# ultra_wideband.net
KiCad netlist of a schematic drawn in Altium Designer
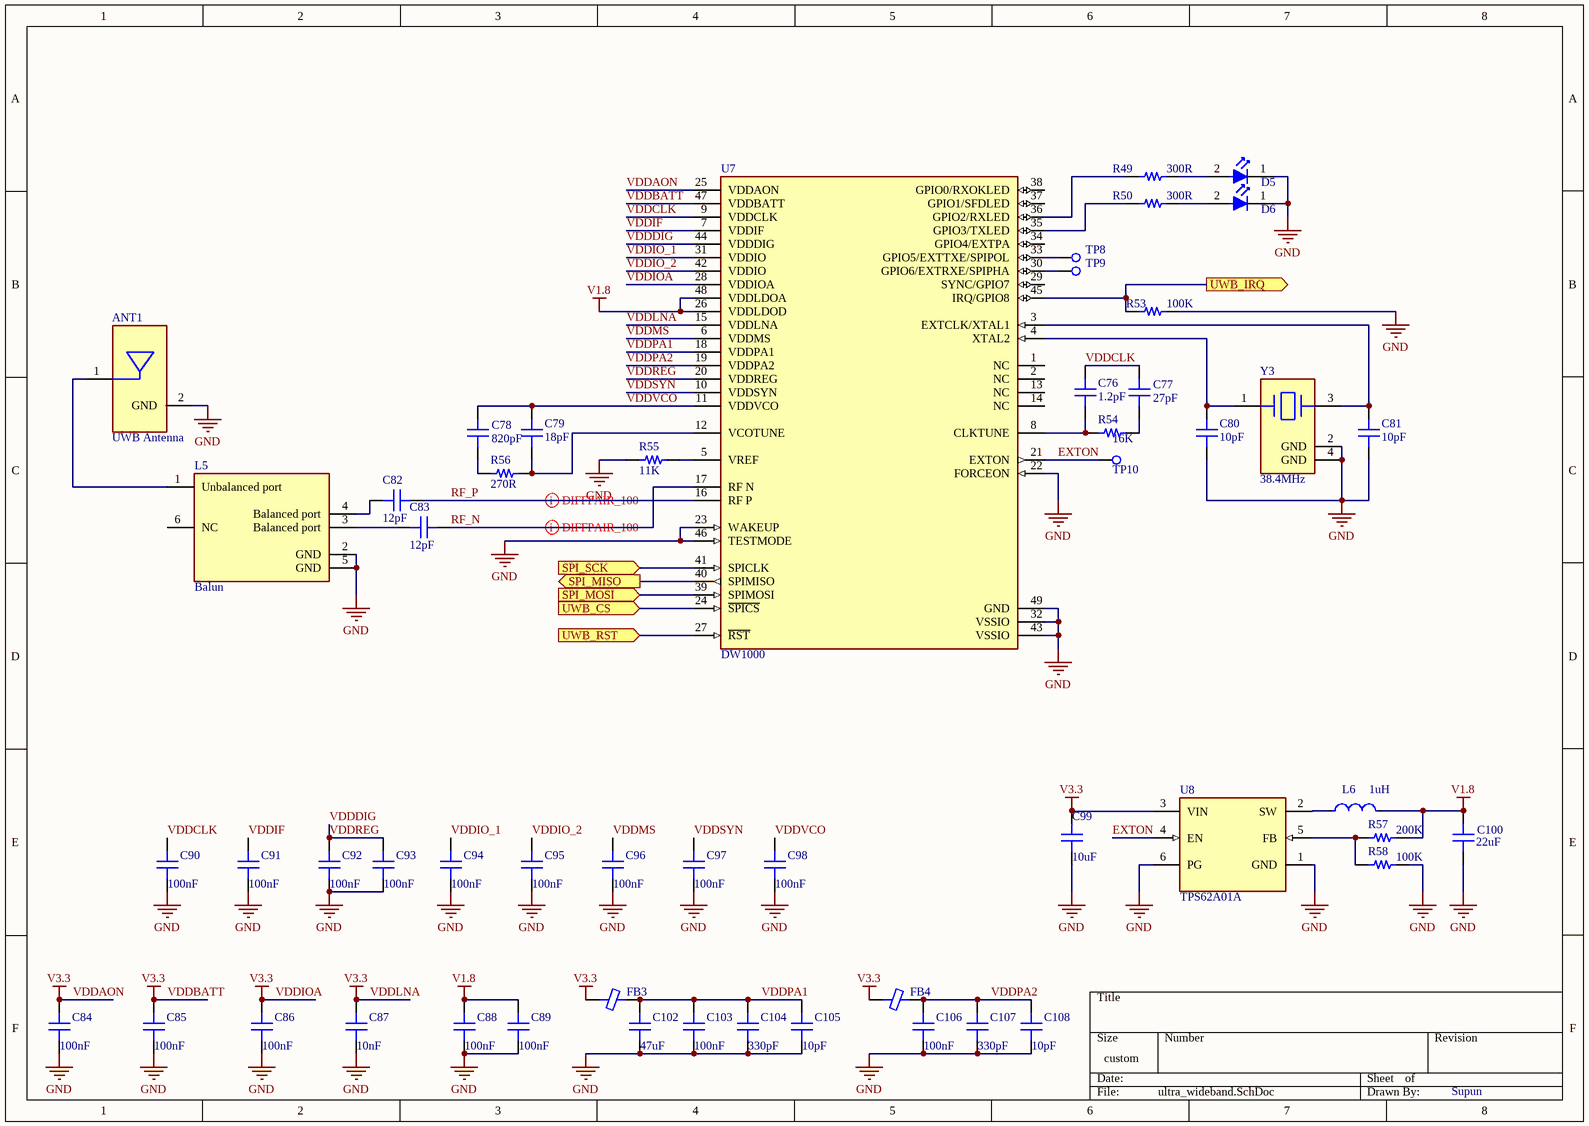
[diagram p0: ultra_wideband.SchDoc]

(export (version "E")
  (design (tool "Eeschema 10.0.6"))
  (components
    (comp (ref "ANT1")
      (value "UWB Antenna")
      (footprint "UWB_ANTENNA_2")
      (description "PCB Antenna")
      (fields (field (name "MF") "SAH"))
      (libsource (lib "Antenna") (part "UWB PCB Antenna"))
    )
    (comp (ref "C76")
      (value "1.2pF")
      (footprint "CAP 0603_1608")
      (description "SMT Capacitor")
      (fields (field (name "MF") "Murata") (field (name "MP") "GRM1885C1H1R2CA01D"))
      (libsource (lib "Capacitor") (part "Capacitor"))
    )
    (comp (ref "C77")
      (value "27pF")
      (footprint "CAP 0603_1608")
      (description "SMT Capacitor")
      (fields (field (name "MF") "Murata") (field (name "MP") "GRM1885C1H270JA01D"))
      (libsource (lib "Capacitor") (part "Capacitor"))
    )
    (comp (ref "C78")
      (value "820pF")
      (footprint "CAP 0603_1608")
      (description "SMT Capacitor")
      (fields (field (name "MF") "Murata") (field (name "MP") "GRM1885C1H821JA01D"))
      (libsource (lib "Capacitor") (part "Capacitor"))
    )
    (comp (ref "C79")
      (value "18pF")
      (footprint "CAP 0603_1608")
      (description "SMT Capacitor")
      (fields (field (name "MF") "Murata") (field (name "MP") "GRM1885C1H180JA01J"))
      (libsource (lib "Capacitor") (part "Capacitor"))
    )
    (comp (ref "C80")
      (value "10pF")
      (footprint "CAP 0603_1608")
      (description "SMT Capacitor")
      (fields (field (name "MF") "Murata") (field (name "MP") "GRM1885C1H100GA01D"))
      (libsource (lib "Capacitor") (part "Capacitor"))
    )
    (comp (ref "C81")
      (value "10pF")
      (footprint "CAP 0603_1608")
      (description "SMT Capacitor")
      (fields (field (name "MF") "Murata") (field (name "MP") "GRM1885C1H100GA01D"))
      (libsource (lib "Capacitor") (part "Capacitor"))
    )
    (comp (ref "C82")
      (value "12pF")
      (footprint "CAP 0603_1608")
      (description "SMT Capacitor")
      (fields (field (name "MF") "Murata") (field (name "MP") "GRM1885C1H120JA01J"))
      (libsource (lib "Capacitor") (part "Capacitor"))
    )
    (comp (ref "C83")
      (value "12pF")
      (footprint "CAP 0603_1608")
      (description "SMT Capacitor")
      (fields (field (name "MF") "Murata") (field (name "MP") "GRM1885C1H120JA01J"))
      (libsource (lib "Capacitor") (part "Capacitor"))
    )
    (comp (ref "C84")
      (value "100nF")
      (footprint "CAP 0603_1608")
      (description "SMT Capacitor")
      (fields (field (name "MF") "TDK") (field (name "MP") "CGA3E2X7R1E104K080AA"))
      (libsource (lib "Capacitor") (part "Capacitor"))
    )
    (comp (ref "C85")
      (value "100nF")
      (footprint "CAP 0603_1608")
      (description "SMT Capacitor")
      (fields (field (name "MF") "TDK") (field (name "MP") "CGA3E2X7R1E104K080AA"))
      (libsource (lib "Capacitor") (part "Capacitor"))
    )
    (comp (ref "C86")
      (value "100nF")
      (footprint "CAP 0603_1608")
      (description "SMT Capacitor")
      (fields (field (name "MF") "TDK") (field (name "MP") "CGA3E2X7R1E104K080AA"))
      (libsource (lib "Capacitor") (part "Capacitor"))
    )
    (comp (ref "C87")
      (value "10nF")
      (footprint "CAP 0603_1608")
      (description "SMT Capacitor")
      (fields (field (name "MF") "Murata") (field (name "MP") "GRM1885C1E103JA01D"))
      (libsource (lib "Capacitor") (part "Capacitor"))
    )
    (comp (ref "C88")
      (value "100nF")
      (footprint "CAP 0603_1608")
      (description "SMT Capacitor")
      (fields (field (name "MF") "TDK") (field (name "MP") "CGA3E2X7R1E104K080AA"))
      (libsource (lib "Capacitor") (part "Capacitor"))
    )
    (comp (ref "C89")
      (value "100nF")
      (footprint "CAP 0603_1608")
      (description "SMT Capacitor")
      (fields (field (name "MF") "TDK") (field (name "MP") "CGA3E2X7R1E104K080AA"))
      (libsource (lib "Capacitor") (part "Capacitor"))
    )
    (comp (ref "C90")
      (value "100nF")
      (footprint "CAP 0603_1608")
      (description "SMT Capacitor")
      (fields (field (name "MF") "TDK") (field (name "MP") "CGA3E2X7R1E104K080AA"))
      (libsource (lib "Capacitor") (part "Capacitor"))
    )
    (comp (ref "C91")
      (value "100nF")
      (footprint "CAP 0603_1608")
      (description "SMT Capacitor")
      (fields (field (name "MF") "TDK") (field (name "MP") "CGA3E2X7R1E104K080AA"))
      (libsource (lib "Capacitor") (part "Capacitor"))
    )
    (comp (ref "C92")
      (value "100nF")
      (footprint "CAP 0603_1608")
      (description "SMT Capacitor")
      (fields (field (name "MF") "TDK") (field (name "MP") "CGA3E2X7R1E104K080AA"))
      (libsource (lib "Capacitor") (part "Capacitor"))
    )
    (comp (ref "C93")
      (value "100nF")
      (footprint "CAP 0603_1608")
      (description "SMT Capacitor")
      (fields (field (name "MF") "TDK") (field (name "MP") "CGA3E2X7R1E104K080AA"))
      (libsource (lib "Capacitor") (part "Capacitor"))
    )
    (comp (ref "C94")
      (value "100nF")
      (footprint "CAP 0603_1608")
      (description "SMT Capacitor")
      (fields (field (name "MF") "TDK") (field (name "MP") "CGA3E2X7R1E104K080AA"))
      (libsource (lib "Capacitor") (part "Capacitor"))
    )
    (comp (ref "C95")
      (value "100nF")
      (footprint "CAP 0603_1608")
      (description "SMT Capacitor")
      (fields (field (name "MF") "TDK") (field (name "MP") "CGA3E2X7R1E104K080AA"))
      (libsource (lib "Capacitor") (part "Capacitor"))
    )
    (comp (ref "C96")
      (value "100nF")
      (footprint "CAP 0603_1608")
      (description "SMT Capacitor")
      (fields (field (name "MF") "TDK") (field (name "MP") "CGA3E2X7R1E104K080AA"))
      (libsource (lib "Capacitor") (part "Capacitor"))
    )
    (comp (ref "C97")
      (value "100nF")
      (footprint "CAP 0603_1608")
      (description "SMT Capacitor")
      (fields (field (name "MF") "TDK") (field (name "MP") "CGA3E2X7R1E104K080AA"))
      (libsource (lib "Capacitor") (part "Capacitor"))
    )
    (comp (ref "C98")
      (value "100nF")
      (footprint "CAP 0603_1608")
      (description "SMT Capacitor")
      (fields (field (name "MF") "TDK") (field (name "MP") "CGA3E2X7R1E104K080AA"))
      (libsource (lib "Capacitor") (part "Capacitor"))
    )
    (comp (ref "C99")
      (value "10uF")
      (footprint "CAP 0603_1608")
      (description "SMT Capacitor")
      (fields (field (name "MF") "Murata") (field (name "MP") "GRM188R61C106MAALD"))
      (libsource (lib "Capacitor") (part "Capacitor"))
    )
    (comp (ref "C100")
      (value "22uF")
      (footprint "CAP 0603_1608")
      (description "SMT Capacitor")
      (fields (field (name "MF") "Murata") (field (name "MP") "GRM188R61A226ME15D"))
      (libsource (lib "Capacitor") (part "Capacitor"))
    )
    (comp (ref "C102")
      (value "47uF")
      (footprint "CAP 0603_1608")
      (description "SMT Capacitor")
      (fields (field (name "MF") "Murata") (field (name "MP") "GRM188R60J476ME15D"))
      (libsource (lib "Capacitor") (part "Capacitor"))
    )
    (comp (ref "C103")
      (value "100nF")
      (footprint "CAP 0603_1608")
      (description "SMT Capacitor")
      (fields (field (name "MF") "TDK") (field (name "MP") "CGA3E2X7R1E104K080AA"))
      (libsource (lib "Capacitor") (part "Capacitor"))
    )
    (comp (ref "C104")
      (value "330pF")
      (footprint "CAP 0603_1608")
      (description "SMT Capacitor")
      (fields (field (name "MF") "Murata") (field (name "MP") "GRM1885C1H331JA01D"))
      (libsource (lib "Capacitor") (part "Capacitor"))
    )
    (comp (ref "C105")
      (value "10pF")
      (footprint "CAP 0603_1608")
      (description "SMT Capacitor")
      (fields (field (name "MF") "Murata") (field (name "MP") "GRM1885C1H100GA01D"))
      (libsource (lib "Capacitor") (part "Capacitor"))
    )
    (comp (ref "C106")
      (value "100nF")
      (footprint "CAP 0603_1608")
      (description "SMT Capacitor")
      (fields (field (name "MF") "TDK") (field (name "MP") "CGA3E2X7R1E104K080AA"))
      (libsource (lib "Capacitor") (part "Capacitor"))
    )
    (comp (ref "C107")
      (value "330pF")
      (footprint "CAP 0603_1608")
      (description "SMT Capacitor")
      (fields (field (name "MF") "Murata") (field (name "MP") "GRM1885C1H331JA01D"))
      (libsource (lib "Capacitor") (part "Capacitor"))
    )
    (comp (ref "C108")
      (value "10pF")
      (footprint "CAP 0603_1608")
      (description "SMT Capacitor")
      (fields (field (name "MF") "Murata") (field (name "MP") "GRM1885C1H100GA01D"))
      (libsource (lib "Capacitor") (part "Capacitor"))
    )
    (comp (ref "D5")
      (value "Green")
      (footprint "Würth_Elektronik_0_MFG")
      (description "Led Diffused SMD")
      (fields (field (name "MF") "LiteOn") (field (name "MP") "LTST-C190KGKT"))
      (libsource (lib "Diode") (part "LED SMD"))
    )
    (comp (ref "D6")
      (value "Red")
      (footprint "Würth_Elektronik_0_MFG")
      (description "Led Diffused SMD")
      (fields (field (name "MF") "LiteOn") (field (name "MP") "LTST-C190KRKT"))
      (libsource (lib "Diode") (part "LED SMD"))
    )
    (comp (ref "FB3")
      (value "Ferrite Beads")
      (footprint "Murata_BLM18-0_15-t0_8_MFG")
      (description "SMT Ferrite Chip")
      (fields (field (name "MF") "Murata") (field (name "MP") "BLM18AG601SH1D"))
      (libsource (lib "Passive") (part "Ferrite Chip"))
    )
    (comp (ref "FB4")
      (value "Ferrite Beads")
      (footprint "Murata_BLM18-0_15-t0_8_MFG")
      (description "SMT Ferrite Chip")
      (fields (field (name "MF") "Murata") (field (name "MP") "BLM18AG601SH1D"))
      (libsource (lib "Passive") (part "Ferrite Chip"))
    )
    (comp (ref "L5")
      (value "Balun")
      (footprint "TDK_HHM1595A1_MFG")
      (description "Signal Conditioning LTCC BALUN 3000-8000MHz")
      (fields (field (name "MF") "TDK") (field (name "MP") "HHM1595A1"))
      (libsource (lib "Antenna") (part "HHM1595A1"))
    )
    (comp (ref "L6")
      (value "1uH")
      (footprint "IND 1008_2520")
      (description "Fixed Inductors 2.2uH 20% High Temp AEC-Q200")
      (fields (field (name "MF") "Murata") (field (name "MP") "DFE252012F-1R0M=P2"))
      (libsource (lib "Inductor") (part "Inductor_sm"))
    )
    (comp (ref "R49")
      (value "300R")
      (footprint "RES 0603_1608")
      (description "SMT Resistor")
      (fields (field (name "MF") "YAGEO") (field (name "MP") "AC0603FR-07300RL"))
      (libsource (lib "Resistor") (part "Resistor"))
    )
    (comp (ref "R50")
      (value "300R")
      (footprint "RES 0603_1608")
      (description "SMT Resistor")
      (fields (field (name "MF") "YAGEO") (field (name "MP") "AC0603FR-07300RL"))
      (libsource (lib "Resistor") (part "Resistor"))
    )
    (comp (ref "R53")
      (value "100K")
      (footprint "RES 0603_1608")
      (description "SMT Resistor")
      (fields (field (name "MF") "YAGEO") (field (name "MP") "AC0603FR-07100KL"))
      (libsource (lib "Resistor") (part "Resistor"))
    )
    (comp (ref "R54")
      (value "16K")
      (footprint "RES 0603_1608")
      (description "SMT Resistor")
      (fields (field (name "MF") "YAGEO") (field (name "MP") "AC0603FR-0716KL"))
      (libsource (lib "Resistor") (part "Resistor"))
    )
    (comp (ref "R55")
      (value "11K")
      (footprint "RES 0603_1608")
      (description "SMT Resistor")
      (fields (field (name "MF") "YAGEO") (field (name "MP") "AC0603FR-0711KL"))
      (libsource (lib "Resistor") (part "Resistor"))
    )
    (comp (ref "R56")
      (value "270R")
      (footprint "RES 0603_1608")
      (description "SMT Resistor")
      (fields (field (name "MF") "YAGEO") (field (name "MP") "AC0603FR-07270RL"))
      (libsource (lib "Resistor") (part "Resistor"))
    )
    (comp (ref "R57")
      (value "200K")
      (footprint "RES 0603_1608")
      (description "SMT Resistor")
      (fields (field (name "MF") "YAGEO") (field (name "MP") "AC0603FR-07200KL"))
      (libsource (lib "Resistor") (part "Resistor"))
    )
    (comp (ref "R58")
      (value "100K")
      (footprint "RES 0603_1608")
      (description "SMT Resistor")
      (fields (field (name "MF") "YAGEO") (field (name "MP") "AC0603FR-07100KL"))
      (libsource (lib "Resistor") (part "Resistor"))
    )
    (comp (ref "TP8")
      (value "Test Point")
      (footprint "TPSMD_S1")
      (libsource (lib "Passive") (part "Test Point"))
    )
    (comp (ref "TP9")
      (value "Test Point")
      (footprint "TPSMD_S1")
      (libsource (lib "Passive") (part "Test Point"))
    )
    (comp (ref "TP10")
      (value "Test Point")
      (footprint "TPSMD_S1")
      (libsource (lib "Passive") (part "Test Point"))
    )
    (comp (ref "U7")
      (value "DW1000")
      (footprint "Qorvo_1_IPC_B")
      (fields (field (name "MF") "Qorvo") (field (name "MP") "DW1000-I-TR13"))
      (libsource (lib "UltraWideBand") (part "DW1000"))
    )
    (comp (ref "U8")
      (value "TPS62A01A")
      (footprint "TI SOT-563 DRL")
      (fields (field (name "MF") "Texas Instruments") (field (name "MP") "TPS62A01ADRLR"))
      (libsource (lib "SwitchingRegulators") (part "TPS62A01A"))
    )
    (comp (ref "Y3")
      (value "38.4MHz")
      (footprint "ABRACON ABM8G")
      (description "Crystals AEC-Q200 CRYSTAL 4pin SMD")
      (fields (field (name "MF") "ECS") (field (name "MP") "ECS-384-10-33B-CKY-TR"))
      (libsource (lib "Crystal") (part "Crystal"))
    )
  )
  (nets
    (net (code "1") (name "/EXTON") (class "Default")
      (node (ref "TP10") (pin "1") (pinfunction "TP_1") (pintype "passive"))
      (node (ref "U7") (pin "21") (pinfunction "EXTON_21") (pintype "output"))
      (node (ref "U8") (pin "4") (pinfunction "EN_4") (pintype "input"))
    )
    (net (code "2") (name "/RF_N") (class "Default")
      (node (ref "C83") (pin "1") (pinfunction "1_1") (pintype "passive"))
      (node (ref "U7") (pin "17") (pinfunction "RF_N_17") (pintype "passive"))
    )
    (net (code "3") (name "/RF_P") (class "Default")
      (node (ref "C82") (pin "1") (pinfunction "1_1") (pintype "passive"))
      (node (ref "U7") (pin "16") (pinfunction "RF_P_16") (pintype "passive"))
    )
    (net (code "4") (name "/SPI_MISO") (class "Default")
      (node (ref "U7") (pin "40") (pinfunction "SPIMISO_40") (pintype "output"))
    )
    (net (code "5") (name "/SPI_MOSI") (class "Default")
      (node (ref "U7") (pin "39") (pinfunction "SPIMOSI_39") (pintype "input"))
    )
    (net (code "6") (name "/SPI_SCK") (class "Default")
      (node (ref "U7") (pin "41") (pinfunction "SPICLK_41") (pintype "input"))
    )
    (net (code "7") (name "/UWB_CS") (class "Default")
      (node (ref "U7") (pin "24") (pinfunction "~{SPICS}_24") (pintype "input"))
    )
    (net (code "8") (name "/UWB_IRQ") (class "Default")
      (node (ref "R53") (pin "2") (pinfunction "2_2") (pintype "passive"))
      (node (ref "U7") (pin "45") (pinfunction "IRQ/GPIO8_45") (pintype "bidirectional"))
    )
    (net (code "9") (name "/UWB_RST") (class "Default")
      (node (ref "U7") (pin "27") (pinfunction "~{RST}_27") (pintype "input"))
    )
    (net (code "10") (name "/VDDCLK") (class "Default")
      (node (ref "C76") (pin "2") (pinfunction "2_2") (pintype "passive"))
      (node (ref "C77") (pin "2") (pinfunction "2_2") (pintype "passive"))
      (node (ref "C90") (pin "1") (pinfunction "1_1") (pintype "passive"))
      (node (ref "U7") (pin "9") (pinfunction "VDDCLK_9") (pintype "power_in"))
    )
    (net (code "11") (name "/VDDDIG") (class "Default")
      (node (ref "C92") (pin "1") (pinfunction "1_1") (pintype "passive"))
      (node (ref "C93") (pin "1") (pinfunction "1_1") (pintype "passive"))
      (node (ref "U7") (pin "20") (pinfunction "VDDREG_20") (pintype "power_in"))
      (node (ref "U7") (pin "44") (pinfunction "VDDDIG_44") (pintype "power_in"))
    )
    (net (code "12") (name "/VDDIF") (class "Default")
      (node (ref "C91") (pin "1") (pinfunction "1_1") (pintype "passive"))
      (node (ref "U7") (pin "7") (pinfunction "VDDIF_7") (pintype "power_in"))
    )
    (net (code "13") (name "/VDDIO_1") (class "Default")
      (node (ref "C94") (pin "1") (pinfunction "1_1") (pintype "passive"))
      (node (ref "U7") (pin "31") (pinfunction "VDDIO_31") (pintype "power_in"))
    )
    (net (code "14") (name "/VDDIO_2") (class "Default")
      (node (ref "C95") (pin "1") (pinfunction "1_1") (pintype "passive"))
      (node (ref "U7") (pin "42") (pinfunction "VDDIO_42") (pintype "power_in"))
    )
    (net (code "15") (name "/VDDMS") (class "Default")
      (node (ref "C96") (pin "1") (pinfunction "1_1") (pintype "passive"))
      (node (ref "U7") (pin "6") (pinfunction "VDDMS_6") (pintype "power_in"))
    )
    (net (code "16") (name "/VDDPA1") (class "Default")
      (node (ref "C102") (pin "2") (pinfunction "2_2") (pintype "passive"))
      (node (ref "C103") (pin "1") (pinfunction "1_1") (pintype "passive"))
      (node (ref "C104") (pin "2") (pinfunction "2_2") (pintype "passive"))
      (node (ref "C105") (pin "2") (pinfunction "2_2") (pintype "passive"))
      (node (ref "FB3") (pin "2") (pinfunction "2_2") (pintype "passive"))
      (node (ref "U7") (pin "18") (pinfunction "VDDPA1_18") (pintype "power_in"))
    )
    (net (code "17") (name "/VDDPA2") (class "Default")
      (node (ref "C106") (pin "1") (pinfunction "1_1") (pintype "passive"))
      (node (ref "C107") (pin "2") (pinfunction "2_2") (pintype "passive"))
      (node (ref "C108") (pin "2") (pinfunction "2_2") (pintype "passive"))
      (node (ref "FB4") (pin "2") (pinfunction "2_2") (pintype "passive"))
      (node (ref "U7") (pin "19") (pinfunction "VDDPA2_19") (pintype "power_in"))
    )
    (net (code "18") (name "/VDDSYN") (class "Default")
      (node (ref "C97") (pin "1") (pinfunction "1_1") (pintype "passive"))
      (node (ref "U7") (pin "10") (pinfunction "VDDSYN_10") (pintype "power_in"))
    )
    (net (code "19") (name "/VDDVCO") (class "Default")
      (node (ref "C78") (pin "2") (pinfunction "2_2") (pintype "passive"))
      (node (ref "C79") (pin "2") (pinfunction "2_2") (pintype "passive"))
      (node (ref "C98") (pin "1") (pinfunction "1_1") (pintype "passive"))
      (node (ref "U7") (pin "11") (pinfunction "VDDVCO_11") (pintype "power_in"))
    )
    (net (code "20") (name "GND") (class "Default")
      (node (ref "ANT1") (pin "2") (pinfunction "GND_2") (pintype "passive"))
      (node (ref "C100") (pin "2") (pinfunction "2_2") (pintype "passive"))
      (node (ref "C102") (pin "1") (pinfunction "1_1") (pintype "passive"))
      (node (ref "C103") (pin "2") (pinfunction "2_2") (pintype "passive"))
      (node (ref "C104") (pin "1") (pinfunction "1_1") (pintype "passive"))
      (node (ref "C105") (pin "1") (pinfunction "1_1") (pintype "passive"))
      (node (ref "C106") (pin "2") (pinfunction "2_2") (pintype "passive"))
      (node (ref "C107") (pin "1") (pinfunction "1_1") (pintype "passive"))
      (node (ref "C108") (pin "1") (pinfunction "1_1") (pintype "passive"))
      (node (ref "C80") (pin "1") (pinfunction "1_1") (pintype "passive"))
      (node (ref "C81") (pin "1") (pinfunction "1_1") (pintype "passive"))
      (node (ref "C84") (pin "2") (pinfunction "2_2") (pintype "passive"))
      (node (ref "C85") (pin "2") (pinfunction "2_2") (pintype "passive"))
      (node (ref "C86") (pin "2") (pinfunction "2_2") (pintype "passive"))
      (node (ref "C87") (pin "2") (pinfunction "2_2") (pintype "passive"))
      (node (ref "C88") (pin "2") (pinfunction "2_2") (pintype "passive"))
      (node (ref "C89") (pin "2") (pinfunction "2_2") (pintype "passive"))
      (node (ref "C90") (pin "2") (pinfunction "2_2") (pintype "passive"))
      (node (ref "C91") (pin "2") (pinfunction "2_2") (pintype "passive"))
      (node (ref "C92") (pin "2") (pinfunction "2_2") (pintype "passive"))
      (node (ref "C93") (pin "2") (pinfunction "2_2") (pintype "passive"))
      (node (ref "C94") (pin "2") (pinfunction "2_2") (pintype "passive"))
      (node (ref "C95") (pin "2") (pinfunction "2_2") (pintype "passive"))
      (node (ref "C96") (pin "2") (pinfunction "2_2") (pintype "passive"))
      (node (ref "C97") (pin "2") (pinfunction "2_2") (pintype "passive"))
      (node (ref "C98") (pin "2") (pinfunction "2_2") (pintype "passive"))
      (node (ref "C99") (pin "2") (pinfunction "2_2") (pintype "passive"))
      (node (ref "D5") (pin "1") (pinfunction "C_1") (pintype "passive"))
      (node (ref "D6") (pin "1") (pinfunction "C_1") (pintype "passive"))
      (node (ref "L5") (pin "2") (pinfunction "GND_2") (pintype "power_in"))
      (node (ref "L5") (pin "5") (pinfunction "GND_5") (pintype "power_in"))
      (node (ref "R53") (pin "1") (pinfunction "1_1") (pintype "passive"))
      (node (ref "R55") (pin "1") (pinfunction "1_1") (pintype "passive"))
      (node (ref "R58") (pin "2") (pinfunction "2_2") (pintype "passive"))
      (node (ref "U7") (pin "22") (pinfunction "FORCEON_22") (pintype "input"))
      (node (ref "U7") (pin "23") (pinfunction "WAKEUP_23") (pintype "input"))
      (node (ref "U7") (pin "32") (pinfunction "VSSIO_32") (pintype "power_in"))
      (node (ref "U7") (pin "43") (pinfunction "VSSIO_43") (pintype "power_in"))
      (node (ref "U7") (pin "46") (pinfunction "TESTMODE_46") (pintype "input"))
      (node (ref "U7") (pin "49") (pinfunction "GND_49") (pintype "power_in"))
      (node (ref "U8") (pin "1") (pinfunction "GND_1") (pintype "power_in"))
      (node (ref "U8") (pin "6") (pinfunction "PG_6") (pintype "passive"))
      (node (ref "Y3") (pin "2") (pinfunction "GND_2") (pintype "power_in"))
      (node (ref "Y3") (pin "4") (pinfunction "GND_4") (pintype "power_in"))
    )
    (net (code "21") (name "Net-(C77-Pad1)") (class "Default")
      (node (ref "C77") (pin "1") (pinfunction "1_1") (pintype "passive"))
      (node (ref "R54") (pin "1") (pinfunction "1_1") (pintype "passive"))
    )
    (net (code "22") (name "Net-(C78-Pad1)") (class "Default")
      (node (ref "C78") (pin "1") (pinfunction "1_1") (pintype "passive"))
      (node (ref "R56") (pin "2") (pinfunction "2_2") (pintype "passive"))
    )
    (net (code "23") (name "Net-(C82-Pad2)") (class "Default")
      (node (ref "C82") (pin "2") (pinfunction "2_2") (pintype "passive"))
      (node (ref "L5") (pin "4") (pinfunction "Balanced_port_4") (pintype "passive"))
    )
    (net (code "24") (name "Net-(C83-Pad2)") (class "Default")
      (node (ref "C83") (pin "2") (pinfunction "2_2") (pintype "passive"))
      (node (ref "L5") (pin "3") (pinfunction "Balanced_port_3") (pintype "passive"))
    )
    (net (code "25") (name "Net-(D5-A)") (class "Default")
      (node (ref "D5") (pin "2") (pinfunction "A_2") (pintype "passive"))
      (node (ref "R49") (pin "2") (pinfunction "2_2") (pintype "passive"))
    )
    (net (code "26") (name "Net-(D6-A)") (class "Default")
      (node (ref "D6") (pin "2") (pinfunction "A_2") (pintype "passive"))
      (node (ref "R50") (pin "2") (pinfunction "2_2") (pintype "passive"))
    )
    (net (code "27") (name "Net-(L5-Unbalanced_port)") (class "Default")
      (node (ref "ANT1") (pin "1") (pinfunction "1_1") (pintype "passive"))
      (node (ref "L5") (pin "1") (pinfunction "Unbalanced_port_1") (pintype "passive"))
    )
    (net (code "28") (name "Net-(TP8-TP)") (class "Default")
      (node (ref "TP8") (pin "1") (pinfunction "TP_1") (pintype "passive"))
      (node (ref "U7") (pin "33") (pinfunction "GPIO5/EXTTXE/SPIPOL_33") (pintype "bidirectional"))
    )
    (net (code "29") (name "Net-(TP9-TP)") (class "Default")
      (node (ref "TP9") (pin "1") (pinfunction "TP_1") (pintype "passive"))
      (node (ref "U7") (pin "30") (pinfunction "GPIO6/EXTRXE/SPIPHA_30") (pintype "bidirectional"))
    )
    (net (code "30") (name "Net-(U7-CLKTUNE)") (class "Default")
      (node (ref "C76") (pin "1") (pinfunction "1_1") (pintype "passive"))
      (node (ref "R54") (pin "2") (pinfunction "2_2") (pintype "passive"))
      (node (ref "U7") (pin "8") (pinfunction "CLKTUNE_8") (pintype "passive"))
    )
    (net (code "31") (name "Net-(U7-EXTCLK{slash}XTAL1)") (class "Default")
      (node (ref "C81") (pin "2") (pinfunction "2_2") (pintype "passive"))
      (node (ref "U7") (pin "3") (pinfunction "EXTCLK/XTAL1_3") (pintype "input"))
      (node (ref "Y3") (pin "3") (pinfunction "3_3") (pintype "passive"))
    )
    (net (code "32") (name "Net-(U7-GPIO2{slash}RXLED)") (class "Default")
      (node (ref "R49") (pin "1") (pinfunction "1_1") (pintype "passive"))
      (node (ref "U7") (pin "36") (pinfunction "GPIO2/RXLED_36") (pintype "bidirectional"))
    )
    (net (code "33") (name "Net-(U7-GPIO3{slash}TXLED)") (class "Default")
      (node (ref "R50") (pin "1") (pinfunction "1_1") (pintype "passive"))
      (node (ref "U7") (pin "35") (pinfunction "GPIO3/TXLED_35") (pintype "bidirectional"))
    )
    (net (code "34") (name "Net-(U7-VCOTUNE)") (class "Default")
      (node (ref "C79") (pin "1") (pinfunction "1_1") (pintype "passive"))
      (node (ref "R56") (pin "1") (pinfunction "1_1") (pintype "passive"))
      (node (ref "U7") (pin "12") (pinfunction "VCOTUNE_12") (pintype "power_in"))
    )
    (net (code "35") (name "Net-(U7-VREF)") (class "Default")
      (node (ref "R55") (pin "2") (pinfunction "2_2") (pintype "passive"))
      (node (ref "U7") (pin "5") (pinfunction "VREF_5") (pintype "passive"))
    )
    (net (code "36") (name "Net-(U7-XTAL2)") (class "Default")
      (node (ref "C80") (pin "2") (pinfunction "2_2") (pintype "passive"))
      (node (ref "U7") (pin "4") (pinfunction "XTAL2_4") (pintype "input"))
      (node (ref "Y3") (pin "1") (pinfunction "1_1") (pintype "passive"))
    )
    (net (code "37") (name "Net-(U8-FB)") (class "Default")
      (node (ref "R57") (pin "1") (pinfunction "1_1") (pintype "passive"))
      (node (ref "R58") (pin "1") (pinfunction "1_1") (pintype "passive"))
      (node (ref "U8") (pin "5") (pinfunction "FB_5") (pintype "input"))
    )
    (net (code "38") (name "Net-(U8-SW)") (class "Default")
      (node (ref "L6") (pin "1") (pinfunction "1_1") (pintype "passive"))
      (node (ref "U8") (pin "2") (pinfunction "SW_2") (pintype "power_in"))
    )
    (net (code "39") (name "V1.8") (class "Default")
      (node (ref "C100") (pin "1") (pinfunction "1_1") (pintype "passive"))
      (node (ref "C88") (pin "1") (pinfunction "1_1") (pintype "passive"))
      (node (ref "C89") (pin "1") (pinfunction "1_1") (pintype "passive"))
      (node (ref "L6") (pin "2") (pinfunction "2_2") (pintype "passive"))
      (node (ref "R57") (pin "2") (pinfunction "2_2") (pintype "passive"))
      (node (ref "U7") (pin "26") (pinfunction "VDDLDOD_26") (pintype "power_in"))
      (node (ref "U7") (pin "48") (pinfunction "VDDLDOA_48") (pintype "power_in"))
    )
    (net (code "40") (name "V3.3") (class "Default")
      (node (ref "C84") (pin "1") (pinfunction "1_1") (pintype "passive"))
      (node (ref "C85") (pin "1") (pinfunction "1_1") (pintype "passive"))
      (node (ref "C86") (pin "1") (pinfunction "1_1") (pintype "passive"))
      (node (ref "C87") (pin "1") (pinfunction "1_1") (pintype "passive"))
      (node (ref "C99") (pin "1") (pinfunction "1_1") (pintype "passive"))
      (node (ref "FB3") (pin "1") (pinfunction "1_1") (pintype "passive"))
      (node (ref "FB4") (pin "1") (pinfunction "1_1") (pintype "passive"))
      (node (ref "U7") (pin "15") (pinfunction "VDDLNA_15") (pintype "power_in"))
      (node (ref "U7") (pin "25") (pinfunction "VDDAON_25") (pintype "power_in"))
      (node (ref "U7") (pin "28") (pinfunction "VDDIOA_28") (pintype "power_in"))
      (node (ref "U7") (pin "47") (pinfunction "VDDBATT_47") (pintype "power_in"))
      (node (ref "U8") (pin "3") (pinfunction "VIN_3") (pintype "power_in"))
    )
    (net (code "41") (name "unconnected-(L5-NC-Pad6)") (class "Default")
      (node (ref "L5") (pin "6") (pinfunction "NC_6") (pintype "passive"))
    )
    (net (code "42") (name "unconnected-(U7-GPIO0{slash}RXOKLED-Pad38)") (class "Default")
      (node (ref "U7") (pin "38") (pinfunction "GPIO0/RXOKLED_38") (pintype "bidirectional"))
    )
    (net (code "43") (name "unconnected-(U7-GPIO1{slash}SFDLED-Pad37)") (class "Default")
      (node (ref "U7") (pin "37") (pinfunction "GPIO1/SFDLED_37") (pintype "bidirectional"))
    )
    (net (code "44") (name "unconnected-(U7-GPIO4{slash}EXTPA-Pad34)") (class "Default")
      (node (ref "U7") (pin "34") (pinfunction "GPIO4/EXTPA_34") (pintype "bidirectional"))
    )
    (net (code "45") (name "unconnected-(U7-NC-Pad1)") (class "Default")
      (node (ref "U7") (pin "1") (pinfunction "NC_1") (pintype "passive"))
    )
    (net (code "46") (name "unconnected-(U7-NC-Pad2)") (class "Default")
      (node (ref "U7") (pin "2") (pinfunction "NC_2") (pintype "passive"))
    )
    (net (code "47") (name "unconnected-(U7-NC-Pad13)") (class "Default")
      (node (ref "U7") (pin "13") (pinfunction "NC_13") (pintype "passive"))
    )
    (net (code "48") (name "unconnected-(U7-NC-Pad14)") (class "Default")
      (node (ref "U7") (pin "14") (pinfunction "NC_14") (pintype "passive"))
    )
    (net (code "49") (name "unconnected-(U7-SYNC{slash}GPIO7-Pad29)") (class "Default")
      (node (ref "U7") (pin "29") (pinfunction "SYNC/GPIO7_29") (pintype "bidirectional"))
    )
  )
)
